# SmartTokens_Microcontroller.net
KiCad netlist of a schematic drawn in Altium Designer
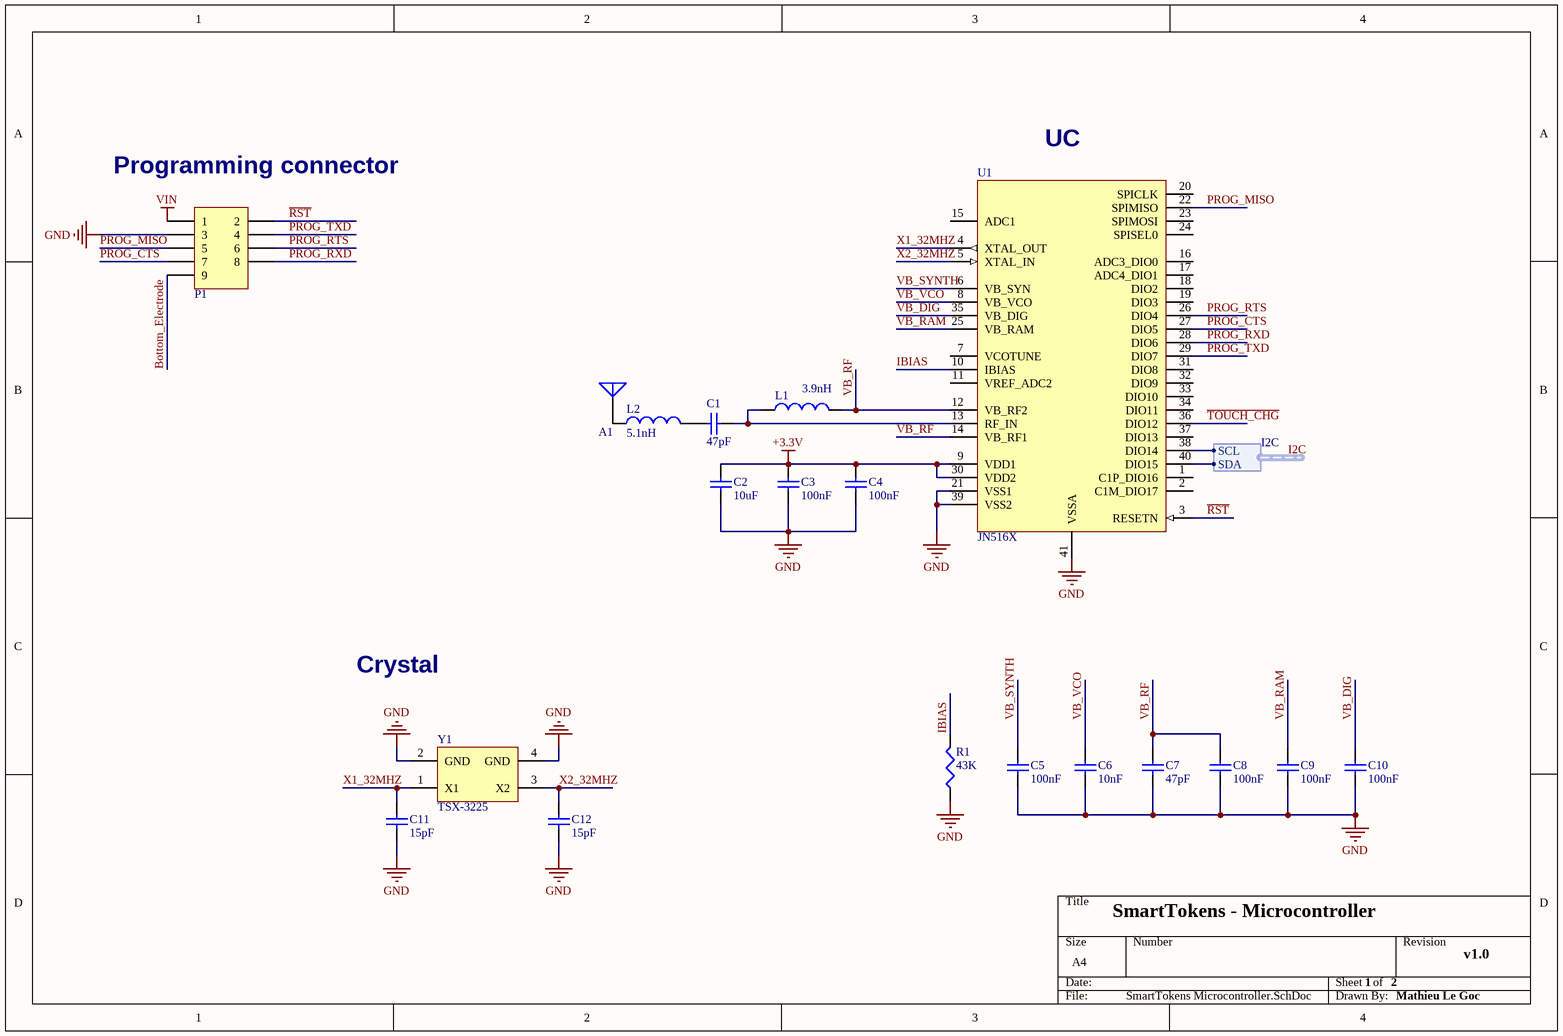
[diagram p0: SmartTokens Microcontroller.SchDoc]

(export (version "E")
  (design (tool "Eeschema 10.0.6"))
  (components
    (comp (ref "A1")
      (value "2450AT18A100")
      (footprint "SmartTokens:2450AT18A100")
      (description "JOHANSON TECHNOLOGY  2450AT18A100E  ANTENNA, CERAMIC, 2.45GHZ")
      (libsource (lib "SmartTokens") (part "2450AT18A100"))
    )
    (comp (ref "C1")
      (value "47pF")
      (footprint "SmartTokens:0402")
      (description "47pF 0402 NP0 50V ±5%")
      (libsource (lib "SmartTokens") (part "47pF"))
    )
    (comp (ref "C2")
      (value "10uF")
      (footprint "SmartTokens:0603")
      (description "10uF 0603 X5R 6.3V ±20%")
      (libsource (lib "SmartTokens") (part "10uF (cheap)"))
    )
    (comp (ref "C3")
      (value "100nF")
      (footprint "SmartTokens:0402")
      (description "100nF 0402 X7R 16V ±10%")
      (libsource (lib "SmartTokens") (part "100nF (cheap)"))
    )
    (comp (ref "C4")
      (value "100nF")
      (footprint "SmartTokens:0402")
      (description "100nF 0402 X7R 16V ±10%")
      (libsource (lib "SmartTokens") (part "100nF (cheap)"))
    )
    (comp (ref "C5")
      (value "100nF")
      (footprint "SmartTokens:0402")
      (description "100nF 0402 X7R 16V ±10%")
      (libsource (lib "SmartTokens") (part "100nF (cheap)"))
    )
    (comp (ref "C6")
      (value "10nF")
      (footprint "SmartTokens:0402")
      (description "10nF 0402 X7R 25V ±5%")
      (libsource (lib "SmartTokens") (part "10nF"))
    )
    (comp (ref "C7")
      (value "47pF")
      (footprint "SmartTokens:0402")
      (description "47pF 0402 NP0 50V ±5%")
      (libsource (lib "SmartTokens") (part "47pF"))
    )
    (comp (ref "C8")
      (value "100nF")
      (footprint "SmartTokens:0402")
      (description "100nF 0402 X7R 16V ±10%")
      (libsource (lib "SmartTokens") (part "100nF (cheap)"))
    )
    (comp (ref "C9")
      (value "100nF")
      (footprint "SmartTokens:0402")
      (description "100nF 0402 X7R 16V ±10%")
      (libsource (lib "SmartTokens") (part "100nF (cheap)"))
    )
    (comp (ref "C10")
      (value "100nF")
      (footprint "SmartTokens:0402")
      (description "100nF 0402 X7R 16V ±10%")
      (libsource (lib "SmartTokens") (part "100nF (cheap)"))
    )
    (comp (ref "C11")
      (value "15pF")
      (footprint "SmartTokens:0402")
      (description "15pF 0402 NP0 50V ±5%")
      (libsource (lib "SmartTokens") (part "15pF"))
    )
    (comp (ref "C12")
      (value "15pF")
      (footprint "SmartTokens:0402")
      (description "15pF 0402 NP0 50V ±5%")
      (libsource (lib "SmartTokens") (part "15pF"))
    )
    (comp (ref "L1")
      (value "3.9nH")
      (footprint "SmartTokens:0402")
      (description "MURATA - LQP15MN3N9B02D - 3.9NH ±0.1NH 0402")
      (fields (field (name "Comment") "3.9NH  0402 MURATA"))
      (libsource (lib "SmartTokens") (part "3.9NH 0402 ±0.1NH"))
    )
    (comp (ref "L2")
      (value "5.1nH")
      (footprint "SmartTokens:0402")
      (description "MURATA - LQP15MN5N1B02D - 5.1NH ±0.1NH 0402")
      (fields (field (name "Comment") "5.1NH  0402 MURATA"))
      (libsource (lib "SmartTokens") (part "5.1NH 0402 ±0.1NH"))
    )
    (comp (ref "P1")
      (value "HEADER 4X2+1 0.05\"")
      (footprint "SmartTokens:HEADER 4X2+1 0.05\"")
      (libsource (lib "SmartTokens") (part "HEADER 4X2+1 0.05{dblquote}"))
    )
    (comp (ref "R1")
      (value "43K")
      (footprint "SmartTokens:0402")
      (description "43K 0402 1/16W ±1%")
      (libsource (lib "SmartTokens") (part "43K"))
    )
    (comp (ref "U1")
      (value "JN516X")
      (footprint "SmartTokens:QFN50P600X600X100_HS-41N")
      (description "IEEE802.15.4 Wireless Microcontroller")
      (libsource (lib "SmartTokens") (part "JN516X"))
    )
    (comp (ref "Y1")
      (value "TSX-3225")
      (footprint "SmartTokens:TSX-3225")
      (description "EPSON - TSX-3225, 32MHZ, 10PPM, 9PF - CRYSTAL, TSX-3225, 32MHZ, 10PPM, 9PF")
      (libsource (lib "SmartTokens") (part "TSX-3225"))
    )
  )
  (nets
    (net (code "2") (name "+3.3V") (class "Default")
      (node (ref "C2") (pin "2") (pinfunction "2_2") (pintype "passive"))
      (node (ref "C3") (pin "2") (pinfunction "2_2") (pintype "passive"))
      (node (ref "C4") (pin "2") (pinfunction "2_2") (pintype "passive"))
      (node (ref "U1") (pin "30") (pinfunction "VDD2_30") (pintype "power_in"))
      (node (ref "U1") (pin "9") (pinfunction "VDD1_9") (pintype "power_in"))
    )
    (net (code "3") (name "/Bottom_Electrode") (class "Default")
      (node (ref "P1") (pin "9") (pinfunction "9_9") (pintype "passive"))
    )
    (net (code "5") (name "/IBIAS") (class "Default")
      (node (ref "R1") (pin "2") (pinfunction "2_2") (pintype "passive"))
      (node (ref "U1") (pin "10") (pinfunction "IBIAS_10") (pintype "passive"))
    )
    (net (code "6") (name "/PROG_CTS") (class "Default")
      (node (ref "P1") (pin "7") (pinfunction "7_7") (pintype "passive"))
      (node (ref "U1") (pin "27") (pinfunction "DIO5_27") (pintype "passive"))
    )
    (net (code "7") (name "/PROG_MISO") (class "Default")
      (node (ref "P1") (pin "5") (pinfunction "5_5") (pintype "passive"))
      (node (ref "U1") (pin "22") (pinfunction "SPIMISO_22") (pintype "passive"))
    )
    (net (code "8") (name "/PROG_RTS") (class "Default")
      (node (ref "P1") (pin "6") (pinfunction "6_6") (pintype "passive"))
      (node (ref "U1") (pin "26") (pinfunction "DIO4_26") (pintype "passive"))
    )
    (net (code "9") (name "/PROG_RXD") (class "Default")
      (node (ref "P1") (pin "8") (pinfunction "8_8") (pintype "passive"))
      (node (ref "U1") (pin "28") (pinfunction "DIO6_28") (pintype "passive"))
    )
    (net (code "10") (name "/PROG_TXD") (class "Default")
      (node (ref "P1") (pin "4") (pinfunction "4_4") (pintype "passive"))
      (node (ref "U1") (pin "29") (pinfunction "DIO7_29") (pintype "passive"))
    )
    (net (code "11") (name "/SCL") (class "Default")
      (node (ref "U1") (pin "38") (pinfunction "DIO14_38") (pintype "passive"))
    )
    (net (code "12") (name "/SDA") (class "Default")
      (node (ref "U1") (pin "40") (pinfunction "DIO15_40") (pintype "passive"))
    )
    (net (code "13") (name "/VB_DIG") (class "Default")
      (node (ref "C10") (pin "2") (pinfunction "2_2") (pintype "passive"))
      (node (ref "U1") (pin "35") (pinfunction "VB_DIG_35") (pintype "passive"))
    )
    (net (code "14") (name "/VB_RAM") (class "Default")
      (node (ref "C9") (pin "2") (pinfunction "2_2") (pintype "passive"))
      (node (ref "U1") (pin "25") (pinfunction "VB_RAM_25") (pintype "passive"))
    )
    (net (code "15") (name "/VB_RF") (class "Default")
      (node (ref "C7") (pin "2") (pinfunction "2_2") (pintype "passive"))
      (node (ref "C8") (pin "2") (pinfunction "2_2") (pintype "passive"))
      (node (ref "L1") (pin "2") (pinfunction "2_2") (pintype "passive"))
      (node (ref "U1") (pin "12") (pinfunction "VB_RF2_12") (pintype "passive"))
      (node (ref "U1") (pin "14") (pinfunction "VB_RF1_14") (pintype "passive"))
    )
    (net (code "16") (name "/VB_SYNTH") (class "Default")
      (node (ref "C5") (pin "2") (pinfunction "2_2") (pintype "passive"))
      (node (ref "U1") (pin "6") (pinfunction "VB_SYN_6") (pintype "passive"))
    )
    (net (code "17") (name "/VB_VCO") (class "Default")
      (node (ref "C6") (pin "2") (pinfunction "2_2") (pintype "passive"))
      (node (ref "U1") (pin "8") (pinfunction "VB_VCO_8") (pintype "passive"))
    )
    (net (code "18") (name "/X1_32MHZ") (class "Default")
      (node (ref "C11") (pin "2") (pinfunction "2_2") (pintype "passive"))
      (node (ref "U1") (pin "4") (pinfunction "XTAL_OUT_4") (pintype "output"))
      (node (ref "Y1") (pin "1") (pinfunction "X1_1") (pintype "passive"))
    )
    (net (code "19") (name "/X2_32MHZ") (class "Default")
      (node (ref "C12") (pin "2") (pinfunction "2_2") (pintype "passive"))
      (node (ref "U1") (pin "5") (pinfunction "XTAL_IN_5") (pintype "input"))
      (node (ref "Y1") (pin "3") (pinfunction "X2_3") (pintype "passive"))
    )
    (net (code "20") (name "/~{RST}") (class "Default")
      (node (ref "P1") (pin "2") (pinfunction "2_2") (pintype "passive"))
      (node (ref "U1") (pin "3") (pinfunction "RESETN_3") (pintype "input"))
    )
    (net (code "21") (name "/~{TOUCH_CHG}") (class "Default")
      (node (ref "U1") (pin "36") (pinfunction "DIO12_36") (pintype "passive"))
    )
    (net (code "22") (name "GND") (class "Default")
      (node (ref "C10") (pin "1") (pinfunction "1_1") (pintype "passive"))
      (node (ref "C11") (pin "1") (pinfunction "1_1") (pintype "passive"))
      (node (ref "C12") (pin "1") (pinfunction "1_1") (pintype "passive"))
      (node (ref "C2") (pin "1") (pinfunction "1_1") (pintype "passive"))
      (node (ref "C3") (pin "1") (pinfunction "1_1") (pintype "passive"))
      (node (ref "C4") (pin "1") (pinfunction "1_1") (pintype "passive"))
      (node (ref "C5") (pin "1") (pinfunction "1_1") (pintype "passive"))
      (node (ref "C6") (pin "1") (pinfunction "1_1") (pintype "passive"))
      (node (ref "C7") (pin "1") (pinfunction "1_1") (pintype "passive"))
      (node (ref "C8") (pin "1") (pinfunction "1_1") (pintype "passive"))
      (node (ref "C9") (pin "1") (pinfunction "1_1") (pintype "passive"))
      (node (ref "P1") (pin "3") (pinfunction "3_3") (pintype "passive"))
      (node (ref "R1") (pin "1") (pinfunction "1_1") (pintype "passive"))
      (node (ref "U1") (pin "21") (pinfunction "VSS1_21") (pintype "power_in"))
      (node (ref "U1") (pin "39") (pinfunction "VSS2_39") (pintype "power_in"))
      (node (ref "U1") (pin "41") (pinfunction "VSSA_41") (pintype "power_in"))
      (node (ref "Y1") (pin "2") (pinfunction "GND_2") (pintype "passive"))
      (node (ref "Y1") (pin "4") (pinfunction "GND_4") (pintype "passive"))
    )
    (net (code "23") (name "Net-(A1-A)") (class "Default")
      (node (ref "A1") (pin "1") (pinfunction "A_1") (pintype "passive"))
      (node (ref "L2") (pin "1") (pinfunction "1_1") (pintype "passive"))
    )
    (net (code "24") (name "Net-(C1-Pad1)") (class "Default")
      (node (ref "C1") (pin "1") (pinfunction "1_1") (pintype "passive"))
      (node (ref "L2") (pin "2") (pinfunction "2_2") (pintype "passive"))
    )
    (net (code "25") (name "Net-(U1-RF_IN)") (class "Default")
      (node (ref "C1") (pin "2") (pinfunction "2_2") (pintype "passive"))
      (node (ref "L1") (pin "1") (pinfunction "1_1") (pintype "passive"))
      (node (ref "U1") (pin "13") (pinfunction "RF_IN_13") (pintype "passive"))
    )
    (net (code "26") (name "VIN") (class "Default")
      (node (ref "P1") (pin "1") (pinfunction "1_1") (pintype "passive"))
    )
    (net (code "27") (name "unconnected-(U1-ADC1-Pad15)") (class "Default")
      (node (ref "U1") (pin "15") (pinfunction "ADC1_15") (pintype "passive"))
    )
    (net (code "28") (name "unconnected-(U1-ADC3_DIO0-Pad16)") (class "Default")
      (node (ref "U1") (pin "16") (pinfunction "ADC3_DIO0_16") (pintype "passive"))
    )
    (net (code "29") (name "unconnected-(U1-ADC4_DIO1-Pad17)") (class "Default")
      (node (ref "U1") (pin "17") (pinfunction "ADC4_DIO1_17") (pintype "passive"))
    )
    (net (code "30") (name "unconnected-(U1-C1M_DIO17-Pad2)") (class "Default")
      (node (ref "U1") (pin "2") (pinfunction "C1M_DIO17_2") (pintype "passive"))
    )
    (net (code "31") (name "unconnected-(U1-C1P_DIO16-Pad1)") (class "Default")
      (node (ref "U1") (pin "1") (pinfunction "C1P_DIO16_1") (pintype "passive"))
    )
    (net (code "32") (name "unconnected-(U1-DIO2-Pad18)") (class "Default")
      (node (ref "U1") (pin "18") (pinfunction "DIO2_18") (pintype "passive"))
    )
    (net (code "33") (name "unconnected-(U1-DIO3-Pad19)") (class "Default")
      (node (ref "U1") (pin "19") (pinfunction "DIO3_19") (pintype "passive"))
    )
    (net (code "34") (name "unconnected-(U1-DIO8-Pad31)") (class "Default")
      (node (ref "U1") (pin "31") (pinfunction "DIO8_31") (pintype "passive"))
    )
    (net (code "35") (name "unconnected-(U1-DIO9-Pad32)") (class "Default")
      (node (ref "U1") (pin "32") (pinfunction "DIO9_32") (pintype "passive"))
    )
    (net (code "36") (name "unconnected-(U1-DIO10-Pad33)") (class "Default")
      (node (ref "U1") (pin "33") (pinfunction "DIO10_33") (pintype "passive"))
    )
    (net (code "37") (name "unconnected-(U1-DIO11-Pad34)") (class "Default")
      (node (ref "U1") (pin "34") (pinfunction "DIO11_34") (pintype "passive"))
    )
    (net (code "38") (name "unconnected-(U1-DIO13-Pad37)") (class "Default")
      (node (ref "U1") (pin "37") (pinfunction "DIO13_37") (pintype "passive"))
    )
    (net (code "39") (name "unconnected-(U1-SPICLK-Pad20)") (class "Default")
      (node (ref "U1") (pin "20") (pinfunction "SPICLK_20") (pintype "passive"))
    )
    (net (code "40") (name "unconnected-(U1-SPIMOSI-Pad23)") (class "Default")
      (node (ref "U1") (pin "23") (pinfunction "SPIMOSI_23") (pintype "passive"))
    )
    (net (code "41") (name "unconnected-(U1-SPISEL0-Pad24)") (class "Default")
      (node (ref "U1") (pin "24") (pinfunction "SPISEL0_24") (pintype "passive"))
    )
    (net (code "42") (name "unconnected-(U1-VCOTUNE-Pad7)") (class "Default")
      (node (ref "U1") (pin "7") (pinfunction "VCOTUNE_7") (pintype "passive"))
    )
    (net (code "43") (name "unconnected-(U1-VREF_ADC2-Pad11)") (class "Default")
      (node (ref "U1") (pin "11") (pinfunction "VREF_ADC2_11") (pintype "passive"))
    )
  )
)
